# UPC2standalone2_Vadriano_capacitor_entra.net
KiCad netlist of a schematic drawn in EAGLE
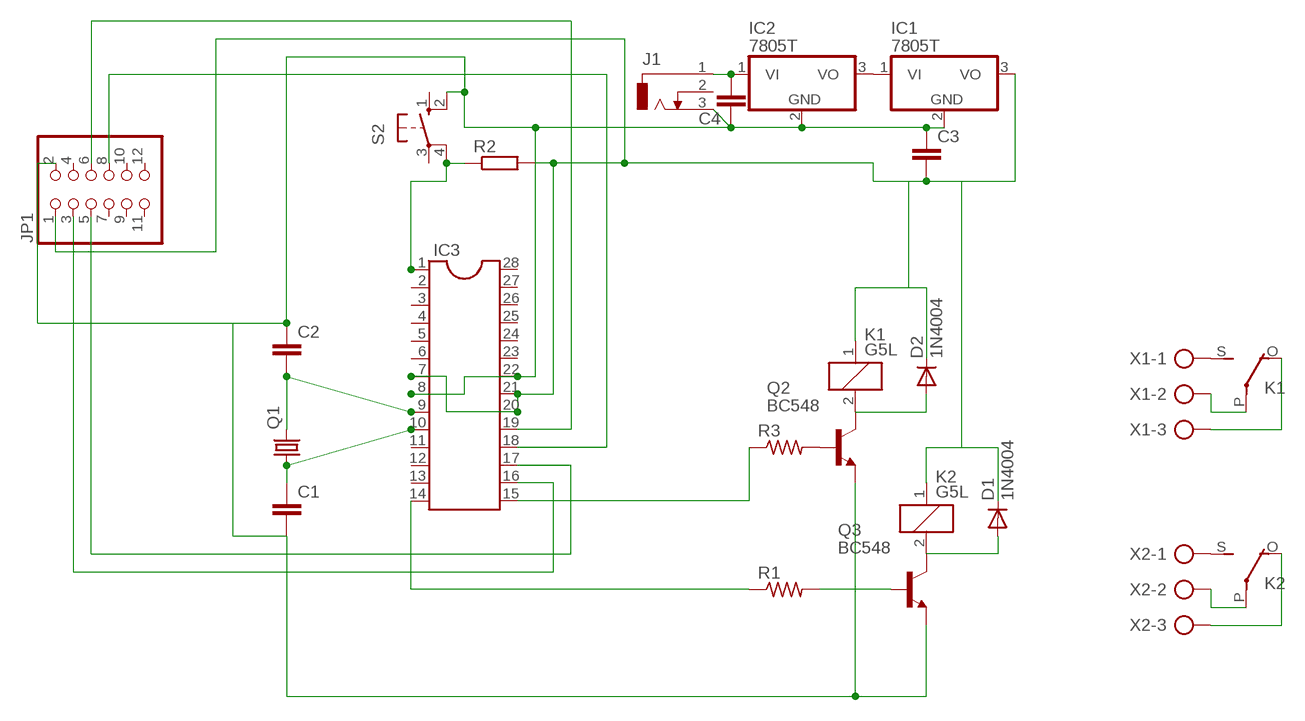
[diagram p0: schematic, sheet 1]

(export (version "E")
  (design (tool "Eeschema 10.0.6"))
  (components
    (comp (ref "C1")
      (value "C5/5")
      (footprint "eagle-import:C5B5")
      (libsource (lib "eagle-import") (part "C5/5"))
    )
    (comp (ref "C2")
      (value "C5/5")
      (footprint "eagle-import:C5B5")
      (libsource (lib "eagle-import") (part "C5/5"))
    )
    (comp (ref "C3")
      (value "C5/5")
      (footprint "eagle-import:C5B5")
      (libsource (lib "eagle-import") (part "C5/5"))
    )
    (comp (ref "C4")
      (value "C5/5")
      (footprint "eagle-import:C5B5")
      (libsource (lib "eagle-import") (part "C5/5"))
    )
    (comp (ref "D1")
      (value "1N4004")
      (footprint "eagle-import:DO41-10")
      (libsource (lib "eagle-import") (part "1N4004"))
    )
    (comp (ref "D2")
      (value "1N4004")
      (footprint "eagle-import:DO41-10")
      (libsource (lib "eagle-import") (part "1N4004"))
    )
    (comp (ref "IC1")
      (value "7805T")
      (footprint "eagle-import:TO220H")
      (libsource (lib "eagle-import") (part "78T05"))
    )
    (comp (ref "IC2")
      (value "7805T")
      (footprint "eagle-import:TO220H")
      (libsource (lib "eagle-import") (part "78T05"))
    )
    (comp (ref "IC3")
      (value "DIL28-3")
      (footprint "eagle-import:DIL28-3")
      (libsource (lib "eagle-import") (part "DIL28-3"))
    )
    (comp (ref "J1")
      (value "DCJ0303")
      (footprint "eagle-import:DCJ0303")
      (libsource (lib "eagle-import") (part "DCJ0303"))
    )
    (comp (ref "JP1")
      (value "PINHD-2X6")
      (footprint "eagle-import:2X06")
      (libsource (lib "eagle-import") (part "PINHD-2X6"))
    )
    (comp (ref "K1")
      (value "G5L")
      (footprint "eagle-import:G5LE")
      (libsource (lib "eagle-import") (part "G5L"))
    )
    (comp (ref "K2")
      (value "G5L")
      (footprint "eagle-import:G5LE")
      (libsource (lib "eagle-import") (part "G5L"))
    )
    (comp (ref "Q1")
      (value "CRYSTALHC49U70")
      (footprint "eagle-import:HC49U70")
      (libsource (lib "eagle-import") (part "CRYSTALHC49U70"))
    )
    (comp (ref "Q2")
      (value "BC548")
      (footprint "eagle-import:TO92-EBC")
      (libsource (lib "eagle-import") (part "BC548"))
    )
    (comp (ref "Q3")
      (value "BC548")
      (footprint "eagle-import:TO92-EBC")
      (libsource (lib "eagle-import") (part "BC548"))
    )
    (comp (ref "R1")
      (value "R-US_0207/10")
      (footprint "eagle-import:0207_10")
      (libsource (lib "eagle-import") (part "R-US_0207/10"))
    )
    (comp (ref "R2")
      (value "R-EU_0207/10")
      (footprint "eagle-import:0207_10")
      (libsource (lib "eagle-import") (part "R-EU_0207/10"))
    )
    (comp (ref "R3")
      (value "R-US_0207/10")
      (footprint "eagle-import:0207_10")
      (libsource (lib "eagle-import") (part "R-US_0207/10"))
    )
    (comp (ref "S2")
      (value "10-XX")
      (footprint "eagle-import:B3F-10XX")
      (libsource (lib "eagle-import") (part "10-XX"))
    )
    (comp (ref "X1")
      (value "AK300/3")
      (footprint "eagle-import:AK300_3")
      (libsource (lib "eagle-import") (part "AK300/3"))
    )
    (comp (ref "X2")
      (value "AK300/3")
      (footprint "eagle-import:AK300_3")
      (libsource (lib "eagle-import") (part "AK300/3"))
    )
  )
  (nets
    (net (code "1") (name "Net-(C1-Pad1)") (class "Default")
      (node (ref "C1") (pin "1") (pinfunction "1_1") (pintype "passive"))
      (node (ref "IC3") (pin "10") (pinfunction "10_10") (pintype "passive"))
      (node (ref "Q1") (pin "1") (pinfunction "1_1") (pintype "passive"))
    )
    (net (code "2") (name "Net-(C2-Pad2)") (class "Default")
      (node (ref "C2") (pin "2") (pinfunction "2_2") (pintype "passive"))
      (node (ref "IC3") (pin "9") (pinfunction "9_9") (pintype "passive"))
      (node (ref "Q1") (pin "2") (pinfunction "2_2") (pintype "passive"))
    )
    (net (code "3") (name "Net-(D1-PadA)") (class "Default")
      (node (ref "D1") (pin "A") (pinfunction "A_A") (pintype "passive"))
      (node (ref "K2") (pin "2") (pinfunction "2_2") (pintype "passive"))
      (node (ref "Q3") (pin "C") (pinfunction "C_C") (pintype "passive"))
    )
    (net (code "4") (name "Net-(D2-PadA)") (class "Default")
      (node (ref "D2") (pin "A") (pinfunction "A_A") (pintype "passive"))
      (node (ref "K1") (pin "2") (pinfunction "2_2") (pintype "passive"))
      (node (ref "Q2") (pin "C") (pinfunction "C_C") (pintype "passive"))
    )
    (net (code "5") (name "Net-(IC1-GND)") (class "Default")
      (node (ref "C1") (pin "2") (pinfunction "2_2") (pintype "passive"))
      (node (ref "C2") (pin "1") (pinfunction "1_1") (pintype "passive"))
      (node (ref "C3") (pin "1") (pinfunction "1_1") (pintype "passive"))
      (node (ref "C4") (pin "1") (pinfunction "1_1") (pintype "passive"))
      (node (ref "IC1") (pin "2") (pinfunction "GND_2") (pintype "passive"))
      (node (ref "IC2") (pin "2") (pinfunction "GND_2") (pintype "passive"))
      (node (ref "IC3") (pin "22") (pinfunction "22_22") (pintype "passive"))
      (node (ref "IC3") (pin "8") (pinfunction "8_8") (pintype "passive"))
      (node (ref "J1") (pin "3") (pinfunction "3_3") (pintype "passive"))
      (node (ref "JP1") (pin "2") (pinfunction "2_2") (pintype "passive"))
      (node (ref "Q2") (pin "E") (pinfunction "E_E") (pintype "passive"))
      (node (ref "Q3") (pin "E") (pinfunction "E_E") (pintype "passive"))
      (node (ref "S2") (pin "2") (pinfunction "S1_2") (pintype "passive"))
    )
    (net (code "6") (name "Net-(IC1-VI)") (class "Default")
      (node (ref "IC1") (pin "1") (pinfunction "VI_1") (pintype "input"))
      (node (ref "IC2") (pin "3") (pinfunction "VO_3") (pintype "passive"))
    )
    (net (code "7") (name "Net-(IC1-VO)") (class "Default")
      (node (ref "C3") (pin "2") (pinfunction "2_2") (pintype "passive"))
      (node (ref "D1") (pin "C") (pinfunction "C_C") (pintype "passive"))
      (node (ref "D2") (pin "C") (pinfunction "C_C") (pintype "passive"))
      (node (ref "IC1") (pin "3") (pinfunction "VO_3") (pintype "passive"))
      (node (ref "IC3") (pin "20") (pinfunction "20_20") (pintype "passive"))
      (node (ref "IC3") (pin "21") (pinfunction "21_21") (pintype "passive"))
      (node (ref "IC3") (pin "7") (pinfunction "7_7") (pintype "passive"))
      (node (ref "JP1") (pin "1") (pinfunction "1_1") (pintype "passive"))
      (node (ref "K1") (pin "1") (pinfunction "1_1") (pintype "passive"))
      (node (ref "K2") (pin "1") (pinfunction "1_1") (pintype "passive"))
      (node (ref "R2") (pin "2") (pinfunction "2_2") (pintype "passive"))
    )
    (net (code "8") (name "Net-(IC2-VI)") (class "Default")
      (node (ref "C4") (pin "2") (pinfunction "2_2") (pintype "passive"))
      (node (ref "IC2") (pin "1") (pinfunction "VI_1") (pintype "input"))
      (node (ref "J1") (pin "1") (pinfunction "1_1") (pintype "passive"))
    )
    (net (code "9") (name "Net-(IC3-Pad14)") (class "Default")
      (node (ref "IC3") (pin "14") (pinfunction "14_14") (pintype "passive"))
      (node (ref "R1") (pin "1") (pinfunction "1_1") (pintype "passive"))
    )
    (net (code "10") (name "Net-(IC3-Pad15)") (class "Default")
      (node (ref "IC3") (pin "15") (pinfunction "15_15") (pintype "passive"))
      (node (ref "R3") (pin "1") (pinfunction "1_1") (pintype "passive"))
    )
    (net (code "11") (name "Net-(IC3-Pad16)") (class "Default")
      (node (ref "IC3") (pin "16") (pinfunction "16_16") (pintype "passive"))
      (node (ref "JP1") (pin "3") (pinfunction "3_3") (pintype "passive"))
    )
    (net (code "12") (name "Net-(IC3-Pad17)") (class "Default")
      (node (ref "IC3") (pin "17") (pinfunction "17_17") (pintype "passive"))
      (node (ref "JP1") (pin "5") (pinfunction "5_5") (pintype "passive"))
    )
    (net (code "13") (name "Net-(IC3-Pad18)") (class "Default")
      (node (ref "IC3") (pin "18") (pinfunction "18_18") (pintype "passive"))
      (node (ref "JP1") (pin "8") (pinfunction "8_8") (pintype "passive"))
    )
    (net (code "14") (name "Net-(IC3-Pad19)") (class "Default")
      (node (ref "IC3") (pin "19") (pinfunction "19_19") (pintype "passive"))
      (node (ref "JP1") (pin "6") (pinfunction "6_6") (pintype "passive"))
    )
    (net (code "15") (name "Net-(Q2-PadB)") (class "Default")
      (node (ref "Q2") (pin "B") (pinfunction "B_B") (pintype "passive"))
      (node (ref "R3") (pin "2") (pinfunction "2_2") (pintype "passive"))
    )
    (net (code "16") (name "Net-(Q3-PadB)") (class "Default")
      (node (ref "Q3") (pin "B") (pinfunction "B_B") (pintype "passive"))
      (node (ref "R1") (pin "2") (pinfunction "2_2") (pintype "passive"))
    )
    (net (code "17") (name "Net-(S2-P1)") (class "Default")
      (node (ref "IC3") (pin "1") (pinfunction "1_1") (pintype "passive"))
      (node (ref "R2") (pin "1") (pinfunction "1_1") (pintype "passive"))
      (node (ref "S2") (pin "4") (pinfunction "P1_4") (pintype "passive"))
    )
    (net (code "18") (name "Net-(X1A-KL)") (class "Default")
      (node (ref "K1") (pin "S") (pinfunction "S_S") (pintype "passive"))
      (node (ref "X1") (pin "1") (pinfunction "KL_1") (pintype "passive"))
    )
    (net (code "19") (name "Net-(X1B-KL)") (class "Default")
      (node (ref "K1") (pin "P") (pinfunction "P_P") (pintype "passive"))
      (node (ref "X1") (pin "2") (pinfunction "KL_2") (pintype "passive"))
    )
    (net (code "20") (name "Net-(X1C-KL)") (class "Default")
      (node (ref "K1") (pin "O") (pinfunction "O_O") (pintype "passive"))
      (node (ref "X1") (pin "3") (pinfunction "KL_3") (pintype "passive"))
    )
    (net (code "21") (name "Net-(X2A-KL)") (class "Default")
      (node (ref "K2") (pin "S") (pinfunction "S_S") (pintype "passive"))
      (node (ref "X2") (pin "1") (pinfunction "KL_1") (pintype "passive"))
    )
    (net (code "22") (name "Net-(X2B-KL)") (class "Default")
      (node (ref "K2") (pin "P") (pinfunction "P_P") (pintype "passive"))
      (node (ref "X2") (pin "2") (pinfunction "KL_2") (pintype "passive"))
    )
    (net (code "23") (name "Net-(X2C-KL)") (class "Default")
      (node (ref "K2") (pin "O") (pinfunction "O_O") (pintype "passive"))
      (node (ref "X2") (pin "3") (pinfunction "KL_3") (pintype "passive"))
    )
    (net (code "24") (name "unconnected-(IC3-Pad2)") (class "Default")
      (node (ref "IC3") (pin "2") (pinfunction "2_2") (pintype "passive"))
    )
    (net (code "25") (name "unconnected-(IC3-Pad3)") (class "Default")
      (node (ref "IC3") (pin "3") (pinfunction "3_3") (pintype "passive"))
    )
    (net (code "26") (name "unconnected-(IC3-Pad4)") (class "Default")
      (node (ref "IC3") (pin "4") (pinfunction "4_4") (pintype "passive"))
    )
    (net (code "27") (name "unconnected-(IC3-Pad5)") (class "Default")
      (node (ref "IC3") (pin "5") (pinfunction "5_5") (pintype "passive"))
    )
    (net (code "28") (name "unconnected-(IC3-Pad6)") (class "Default")
      (node (ref "IC3") (pin "6") (pinfunction "6_6") (pintype "passive"))
    )
    (net (code "29") (name "unconnected-(IC3-Pad11)") (class "Default")
      (node (ref "IC3") (pin "11") (pinfunction "11_11") (pintype "passive"))
    )
    (net (code "30") (name "unconnected-(IC3-Pad12)") (class "Default")
      (node (ref "IC3") (pin "12") (pinfunction "12_12") (pintype "passive"))
    )
    (net (code "31") (name "unconnected-(IC3-Pad13)") (class "Default")
      (node (ref "IC3") (pin "13") (pinfunction "13_13") (pintype "passive"))
    )
    (net (code "32") (name "unconnected-(IC3-Pad23)") (class "Default")
      (node (ref "IC3") (pin "23") (pinfunction "23_23") (pintype "passive"))
    )
    (net (code "33") (name "unconnected-(IC3-Pad24)") (class "Default")
      (node (ref "IC3") (pin "24") (pinfunction "24_24") (pintype "passive"))
    )
    (net (code "34") (name "unconnected-(IC3-Pad25)") (class "Default")
      (node (ref "IC3") (pin "25") (pinfunction "25_25") (pintype "passive"))
    )
    (net (code "35") (name "unconnected-(IC3-Pad26)") (class "Default")
      (node (ref "IC3") (pin "26") (pinfunction "26_26") (pintype "passive"))
    )
    (net (code "36") (name "unconnected-(IC3-Pad27)") (class "Default")
      (node (ref "IC3") (pin "27") (pinfunction "27_27") (pintype "passive"))
    )
    (net (code "37") (name "unconnected-(IC3-Pad28)") (class "Default")
      (node (ref "IC3") (pin "28") (pinfunction "28_28") (pintype "passive"))
    )
    (net (code "38") (name "unconnected-(J1-Pad2)") (class "Default")
      (node (ref "J1") (pin "2") (pinfunction "2_2") (pintype "passive"))
    )
    (net (code "39") (name "unconnected-(JP1-Pad4)") (class "Default")
      (node (ref "JP1") (pin "4") (pinfunction "4_4") (pintype "passive"))
    )
    (net (code "40") (name "unconnected-(JP1-Pad7)") (class "Default")
      (node (ref "JP1") (pin "7") (pinfunction "7_7") (pintype "passive"))
    )
    (net (code "41") (name "unconnected-(JP1-Pad9)") (class "Default")
      (node (ref "JP1") (pin "9") (pinfunction "9_9") (pintype "passive"))
    )
    (net (code "42") (name "unconnected-(JP1-Pad10)") (class "Default")
      (node (ref "JP1") (pin "10") (pinfunction "10_10") (pintype "passive"))
    )
    (net (code "43") (name "unconnected-(JP1-Pad11)") (class "Default")
      (node (ref "JP1") (pin "11") (pinfunction "11_11") (pintype "passive"))
    )
    (net (code "44") (name "unconnected-(JP1-Pad12)") (class "Default")
      (node (ref "JP1") (pin "12") (pinfunction "12_12") (pintype "passive"))
    )
    (net (code "45") (name "unconnected-(S2-P-Pad3)") (class "Default")
      (node (ref "S2") (pin "3") (pinfunction "P_3") (pintype "passive"))
    )
    (net (code "46") (name "unconnected-(S2-S-Pad1)") (class "Default")
      (node (ref "S2") (pin "1") (pinfunction "S_1") (pintype "passive"))
    )
  )
)
